# belichter-timer.net
KiCad netlist of a schematic drawn in EAGLE
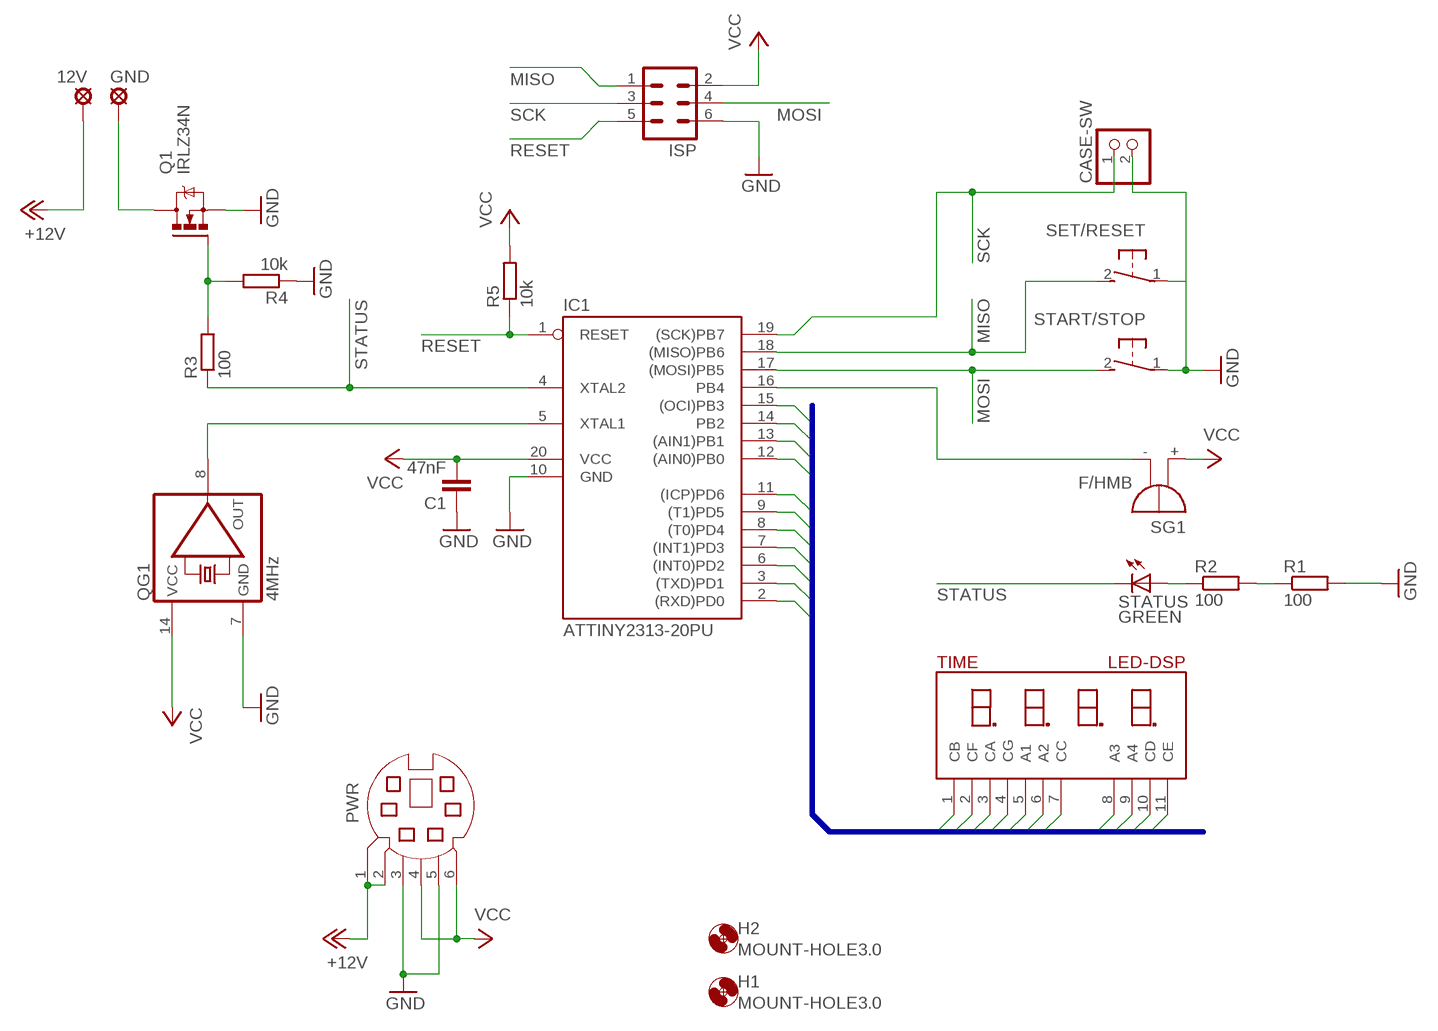
[diagram p0: schematic, sheet 1]

(export (version "E")
  (design (tool "Eeschema 10.0.6"))
  (components
    (comp (ref "12V")
      (value "SE14")
      (footprint "eagle-import:SE14")
      (libsource (lib "eagle-import") (part "SE14"))
    )
    (comp (ref "C1")
      (value "47nF")
      (footprint "eagle-import:C075-032X103")
      (libsource (lib "eagle-import") (part "C-EU075-032X103"))
    )
    (comp (ref "CASE-SW")
      (value "PINHD-1X2")
      (footprint "eagle-import:1X02")
      (libsource (lib "eagle-import") (part "PINHD-1X2"))
    )
    (comp (ref "GND")
      (value "SE14")
      (footprint "eagle-import:SE14")
      (libsource (lib "eagle-import") (part "SE14"))
    )
    (comp (ref "H1")
      (value "MOUNT-HOLE3.0")
      (footprint "eagle-import:3,0")
      (libsource (lib "eagle-import") (part "MOUNT-HOLE3.0"))
    )
    (comp (ref "H2")
      (value "MOUNT-HOLE3.0")
      (footprint "eagle-import:3,0")
      (libsource (lib "eagle-import") (part "MOUNT-HOLE3.0"))
    )
    (comp (ref "IC1")
      (value "ATTINY2313-20PU")
      (footprint "eagle-import:DIL20")
      (libsource (lib "eagle-import") (part "AT90S2313P"))
    )
    (comp (ref "ISP")
      (value "ML6")
      (footprint "eagle-import:ML6")
      (libsource (lib "eagle-import") (part "ML6"))
    )
    (comp (ref "PWR")
      (value "MD06SS")
      (footprint "eagle-import:MDIN06SS")
      (libsource (lib "eagle-import") (part "MD06SS"))
    )
    (comp (ref "Q1")
      (value "IRLZ34N")
      (footprint "eagle-import:TO220BH")
      (libsource (lib "eagle-import") (part "IRLZ44Z"))
    )
    (comp (ref "QG1")
      (value "4MHz")
      (footprint "eagle-import:DIL14S")
      (libsource (lib "eagle-import") (part "QG5860"))
    )
    (comp (ref "R1")
      (value "100")
      (footprint "eagle-import:0204_7")
      (libsource (lib "eagle-import") (part "R-EU_0204/7"))
    )
    (comp (ref "R2")
      (value "100")
      (footprint "eagle-import:0204_7")
      (libsource (lib "eagle-import") (part "R-EU_0204/7"))
    )
    (comp (ref "R3")
      (value "100")
      (footprint "eagle-import:0204_7")
      (libsource (lib "eagle-import") (part "R-EU_0204/7"))
    )
    (comp (ref "R4")
      (value "10k")
      (footprint "eagle-import:0204_7")
      (libsource (lib "eagle-import") (part "R-EU_0204/7"))
    )
    (comp (ref "R5")
      (value "10k")
      (footprint "eagle-import:0204_7")
      (libsource (lib "eagle-import") (part "R-EU_0204/7"))
    )
    (comp (ref "SET/RESET")
      (value "31-XX")
      (footprint "eagle-import:B3F-31XX")
      (fields (field (name "MPN") "B3F-3100"))
      (libsource (lib "eagle-import") (part "31-XX"))
    )
    (comp (ref "SG1")
      (value "F/HMB")
      (footprint "eagle-import:F_HMB")
      (libsource (lib "eagle-import") (part "F/HMB"))
    )
    (comp (ref "START/STOP")
      (value "31-XX")
      (footprint "eagle-import:B3F-31XX")
      (fields (field (name "MPN") "B3F-3100"))
      (libsource (lib "eagle-import") (part "31-XX"))
    )
    (comp (ref "STATUS")
      (value "GREEN")
      (footprint "eagle-import:LED5MM")
      (libsource (lib "eagle-import") (part "LED5MM"))
    )
    (comp (ref "TIME")
      (value "LED-DSP")
      (footprint "eagle-import:LED-DSP")
      (libsource (lib "eagle-import") (part "LED-DSP"))
    )
  )
  (nets
    (net (code "1") (name "+12V") (class "Default")
      (node (ref "12V") (pin "MP") (pinfunction "MP_MP") (pintype "passive"))
      (node (ref "PWR") (pin "1") (pinfunction "1_1") (pintype "passive"))
      (node (ref "PWR") (pin "2") (pinfunction "2_2") (pintype "passive"))
    )
    (net (code "2") (name "/DP0") (class "Default")
      (node (ref "IC1") (pin "11") (pinfunction "(ICP)PD6_11") (pintype "bidirectional"))
      (node (ref "TIME") (pin "7") (pinfunction "CC_7") (pintype "input"))
    )
    (net (code "3") (name "/DP1") (class "Default")
      (node (ref "IC1") (pin "9") (pinfunction "(T1)PD5_9") (pintype "bidirectional"))
      (node (ref "TIME") (pin "6") (pinfunction "A2_6") (pintype "input"))
    )
    (net (code "4") (name "/DP2") (class "Default")
      (node (ref "IC1") (pin "8") (pinfunction "(T0)PD4_8") (pintype "bidirectional"))
      (node (ref "TIME") (pin "5") (pinfunction "A1_5") (pintype "input"))
    )
    (net (code "5") (name "/DP3") (class "Default")
      (node (ref "IC1") (pin "7") (pinfunction "(INT1)PD3_7") (pintype "bidirectional"))
      (node (ref "TIME") (pin "4") (pinfunction "CG_4") (pintype "input"))
    )
    (net (code "6") (name "/DP4") (class "Default")
      (node (ref "IC1") (pin "6") (pinfunction "(INT0)PD2_6") (pintype "bidirectional"))
      (node (ref "TIME") (pin "3") (pinfunction "CA_3") (pintype "input"))
    )
    (net (code "7") (name "/DP5") (class "Default")
      (node (ref "IC1") (pin "3") (pinfunction "(TXD)PD1_3") (pintype "bidirectional"))
      (node (ref "TIME") (pin "2") (pinfunction "CF_2") (pintype "input"))
    )
    (net (code "8") (name "/DP6") (class "Default")
      (node (ref "IC1") (pin "2") (pinfunction "(RXD)PD0_2") (pintype "bidirectional"))
      (node (ref "TIME") (pin "1") (pinfunction "CB_1") (pintype "input"))
    )
    (net (code "9") (name "/DPA") (class "Default")
      (node (ref "IC1") (pin "15") (pinfunction "(OCI)PB3_15") (pintype "bidirectional"))
      (node (ref "TIME") (pin "11") (pinfunction "CE_11") (pintype "input"))
    )
    (net (code "10") (name "/DPB") (class "Default")
      (node (ref "IC1") (pin "14") (pinfunction "PB2_14") (pintype "bidirectional"))
      (node (ref "TIME") (pin "10") (pinfunction "CD_10") (pintype "input"))
    )
    (net (code "11") (name "/DPC") (class "Default")
      (node (ref "IC1") (pin "13") (pinfunction "(AIN1)PB1_13") (pintype "bidirectional"))
      (node (ref "TIME") (pin "9") (pinfunction "A4_9") (pintype "input"))
    )
    (net (code "12") (name "/DPD") (class "Default")
      (node (ref "IC1") (pin "12") (pinfunction "(AIN0)PB0_12") (pintype "bidirectional"))
      (node (ref "TIME") (pin "8") (pinfunction "A3_8") (pintype "input"))
    )
    (net (code "13") (name "/MISO") (class "Default")
      (node (ref "IC1") (pin "18") (pinfunction "(MISO)PB6_18") (pintype "bidirectional"))
      (node (ref "ISP") (pin "1") (pinfunction "1_1") (pintype "passive"))
      (node (ref "SET/RESET") (pin "2") (pinfunction "S_2") (pintype "passive"))
    )
    (net (code "14") (name "/MOSI") (class "Default")
      (node (ref "IC1") (pin "17") (pinfunction "(MOSI)PB5_17") (pintype "bidirectional"))
      (node (ref "ISP") (pin "4") (pinfunction "4_4") (pintype "passive"))
      (node (ref "START/STOP") (pin "2") (pinfunction "S_2") (pintype "passive"))
    )
    (net (code "15") (name "/RESET") (class "Default")
      (node (ref "IC1") (pin "1") (pinfunction "RESET_1") (pintype "bidirectional"))
      (node (ref "ISP") (pin "5") (pinfunction "5_5") (pintype "passive"))
      (node (ref "R5") (pin "1") (pinfunction "1_1") (pintype "passive"))
    )
    (net (code "16") (name "/SCK") (class "Default")
      (node (ref "CASE-SW") (pin "1") (pinfunction "1_1") (pintype "passive"))
      (node (ref "IC1") (pin "19") (pinfunction "(SCK)PB7_19") (pintype "bidirectional"))
      (node (ref "ISP") (pin "3") (pinfunction "3_3") (pintype "passive"))
    )
    (net (code "17") (name "/STATUS") (class "Default")
      (node (ref "IC1") (pin "4") (pinfunction "XTAL2_4") (pintype "bidirectional"))
      (node (ref "R3") (pin "1") (pinfunction "1_1") (pintype "passive"))
      (node (ref "STATUS") (pin "K") (pinfunction "C_K") (pintype "passive"))
    )
    (net (code "18") (name "GND") (class "Default")
      (node (ref "C1") (pin "1") (pinfunction "1_1") (pintype "passive"))
      (node (ref "CASE-SW") (pin "2") (pinfunction "2_2") (pintype "passive"))
      (node (ref "IC1") (pin "10") (pinfunction "GND_10") (pintype "power_in"))
      (node (ref "ISP") (pin "6") (pinfunction "6_6") (pintype "passive"))
      (node (ref "PWR") (pin "3") (pinfunction "3_3") (pintype "passive"))
      (node (ref "PWR") (pin "5") (pinfunction "5_5") (pintype "passive"))
      (node (ref "Q1") (pin "S") (pinfunction "S_S") (pintype "passive"))
      (node (ref "QG1") (pin "7") (pinfunction "GND_7") (pintype "power_in"))
      (node (ref "R1") (pin "2") (pinfunction "2_2") (pintype "passive"))
      (node (ref "R4") (pin "1") (pinfunction "1_1") (pintype "passive"))
      (node (ref "SET/RESET") (pin "1") (pinfunction "P_1") (pintype "passive"))
      (node (ref "START/STOP") (pin "1") (pinfunction "P_1") (pintype "passive"))
    )
    (net (code "19") (name "Net-(GND-PadMP)") (class "Default")
      (node (ref "GND") (pin "MP") (pinfunction "MP_MP") (pintype "passive"))
      (node (ref "Q1") (pin "D") (pinfunction "D_D") (pintype "passive"))
    )
    (net (code "20") (name "Net-(IC1-PB4)") (class "Default")
      (node (ref "IC1") (pin "16") (pinfunction "PB4_16") (pintype "bidirectional"))
      (node (ref "SG1") (pin "-") (pinfunction "-_-") (pintype "passive"))
    )
    (net (code "21") (name "Net-(IC1-XTAL1)") (class "Default")
      (node (ref "IC1") (pin "5") (pinfunction "XTAL1_5") (pintype "bidirectional"))
      (node (ref "QG1") (pin "8") (pinfunction "OUT_8") (pintype "output"))
    )
    (net (code "22") (name "Net-(Q1-PadG)") (class "Default")
      (node (ref "Q1") (pin "G") (pinfunction "G_G") (pintype "passive"))
      (node (ref "R3") (pin "2") (pinfunction "2_2") (pintype "passive"))
      (node (ref "R4") (pin "2") (pinfunction "2_2") (pintype "passive"))
    )
    (net (code "23") (name "Net-(R1-Pad1)") (class "Default")
      (node (ref "R1") (pin "1") (pinfunction "1_1") (pintype "passive"))
      (node (ref "R2") (pin "2") (pinfunction "2_2") (pintype "passive"))
    )
    (net (code "24") (name "Net-(R2-Pad1)") (class "Default")
      (node (ref "R2") (pin "1") (pinfunction "1_1") (pintype "passive"))
      (node (ref "STATUS") (pin "A") (pinfunction "A_A") (pintype "passive"))
    )
    (net (code "25") (name "VCC") (class "Default")
      (node (ref "C1") (pin "2") (pinfunction "2_2") (pintype "passive"))
      (node (ref "IC1") (pin "20") (pinfunction "VCC_20") (pintype "power_in"))
      (node (ref "ISP") (pin "2") (pinfunction "2_2") (pintype "passive"))
      (node (ref "PWR") (pin "4") (pinfunction "4_4") (pintype "passive"))
      (node (ref "PWR") (pin "6") (pinfunction "6_6") (pintype "passive"))
      (node (ref "QG1") (pin "14") (pinfunction "VCC_14") (pintype "power_in"))
      (node (ref "R5") (pin "2") (pinfunction "2_2") (pintype "passive"))
      (node (ref "SG1") (pin "+") (pinfunction "+_+") (pintype "passive"))
    )
  )
)
